# OledAdapter.net
KiCad netlist of a schematic drawn in EAGLE
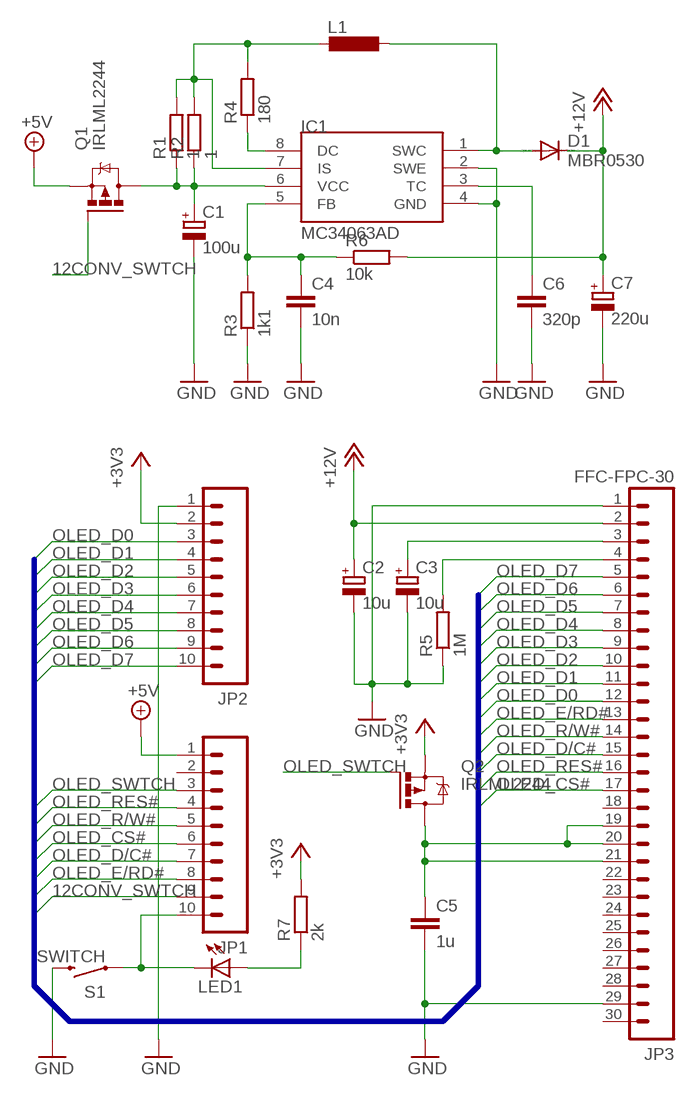
[diagram p0: schematic, sheet 1]

(export (version "E")
  (design (tool "Eeschema 10.0.6"))
  (components
    (comp (ref "C1")
      (value "100u")
      (footprint "eagle-import:UD-6,3X7,7_NICHICON")
      (libsource (lib "eagle-import") (part "CPOL-EUUD-6,3X7,7"))
    )
    (comp (ref "C2")
      (value "10u")
      (footprint "eagle-import:UD-4X5,8_NICHICON")
      (libsource (lib "eagle-import") (part "CPOL-EUUD-4X5,8"))
    )
    (comp (ref "C3")
      (value "10u")
      (footprint "eagle-import:UD-4X5,8_NICHICON")
      (libsource (lib "eagle-import") (part "CPOL-EUUD-4X5,8"))
    )
    (comp (ref "C4")
      (value "10n")
      (footprint "eagle-import:C0805")
      (libsource (lib "eagle-import") (part "C-EUC0805"))
    )
    (comp (ref "C5")
      (value "1u")
      (footprint "eagle-import:C1206")
      (libsource (lib "eagle-import") (part "C-EUC1206"))
    )
    (comp (ref "C6")
      (value "320p")
      (footprint "eagle-import:C0805")
      (libsource (lib "eagle-import") (part "C-EUC0805"))
    )
    (comp (ref "C7")
      (value "220u")
      (footprint "eagle-import:UD-6,3X7,7_NICHICON")
      (libsource (lib "eagle-import") (part "CPOL-EUUD-6,3X7,7"))
    )
    (comp (ref "D1")
      (value "MBR0530")
      (footprint "eagle-import:SOD123")
      (libsource (lib "eagle-import") (part "MBR0520LT"))
    )
    (comp (ref "IC1")
      (value "MC34063AD")
      (footprint "eagle-import:SOIC8")
      (libsource (lib "eagle-import") (part "MC34063AD"))
    )
    (comp (ref "JP1")
      (value "M10SILK_FEMALE_PTH")
      (footprint "eagle-import:1X10")
      (libsource (lib "eagle-import") (part "M10SILK_FEMALE_PTH"))
    )
    (comp (ref "JP2")
      (value "M10SILK_FEMALE_PTH")
      (footprint "eagle-import:1X10")
      (libsource (lib "eagle-import") (part "M10SILK_FEMALE_PTH"))
    )
    (comp (ref "JP3")
      (value "FFC-FPC-30")
      (footprint "eagle-import:FFC-FPC-30V")
      (libsource (lib "eagle-import") (part "FFC-FPC-30"))
    )
    (comp (ref "L1")
      (value "L-EUL8530M")
      (footprint "eagle-import:L8530M")
      (libsource (lib "eagle-import") (part "L-EUL8530M"))
    )
    (comp (ref "LED1")
      (value "LEDSML1206")
      (footprint "eagle-import:SML1206")
      (libsource (lib "eagle-import") (part "LEDSML1206"))
    )
    (comp (ref "Q1")
      (value "IRLML2244")
      (footprint "eagle-import:MICRO3")
      (libsource (lib "eagle-import") (part "IRLML5203"))
    )
    (comp (ref "Q2")
      (value "IRLML2244")
      (footprint "eagle-import:MICRO3")
      (libsource (lib "eagle-import") (part "IRLML5203"))
    )
    (comp (ref "R1")
      (value "1")
      (footprint "eagle-import:R0805")
      (libsource (lib "eagle-import") (part "R-EU_R0805"))
    )
    (comp (ref "R2")
      (value "1")
      (footprint "eagle-import:R0805")
      (libsource (lib "eagle-import") (part "R-EU_R0805"))
    )
    (comp (ref "R3")
      (value "1k1")
      (footprint "eagle-import:R0805")
      (libsource (lib "eagle-import") (part "R-EU_R0805"))
    )
    (comp (ref "R4")
      (value "180")
      (footprint "eagle-import:R0805")
      (libsource (lib "eagle-import") (part "R-EU_R0805"))
    )
    (comp (ref "R5")
      (value "1M")
      (footprint "eagle-import:M1206")
      (libsource (lib "eagle-import") (part "R-EU_M1206"))
    )
    (comp (ref "R6")
      (value "10k")
      (footprint "eagle-import:R0805")
      (libsource (lib "eagle-import") (part "R-EU_R0805"))
    )
    (comp (ref "R7")
      (value "2k")
      (footprint "eagle-import:R0805")
      (libsource (lib "eagle-import") (part "R-EU_R0805"))
    )
    (comp (ref "S1")
      (value "SWITCH")
      (footprint "eagle-import:TACTILE-SWITCH-1101NE")
      (libsource (lib "eagle-import") (part "SWITCH-MOMENTARY-2SMD-1101NE"))
    )
  )
  (nets
    (net (code "1") (name "+3V3") (class "Default")
      (node (ref "JP2") (pin "2") (pinfunction "2_2") (pintype "passive"))
      (node (ref "Q2") (pin "2") (pinfunction "S_2") (pintype "passive"))
      (node (ref "R7") (pin "2") (pinfunction "2_2") (pintype "passive"))
    )
    (net (code "2") (name "+5V") (class "Default")
      (node (ref "JP1") (pin "1") (pinfunction "1_1") (pintype "passive"))
      (node (ref "Q1") (pin "2") (pinfunction "S_2") (pintype "passive"))
    )
    (net (code "3") (name "+12V") (class "Default")
      (node (ref "C2") (pin "+") (pinfunction "+_+") (pintype "passive"))
      (node (ref "C7") (pin "+") (pinfunction "+_+") (pintype "passive"))
      (node (ref "D1") (pin "C") (pinfunction "C_C") (pintype "passive"))
      (node (ref "JP3") (pin "2") (pinfunction "2_2") (pintype "passive"))
      (node (ref "R6") (pin "2") (pinfunction "2_2") (pintype "passive"))
    )
    (net (code "4") (name "/12CONV_SWTCH") (class "Default")
      (node (ref "JP1") (pin "9") (pinfunction "9_9") (pintype "passive"))
      (node (ref "Q1") (pin "1") (pinfunction "G_1") (pintype "passive"))
    )
    (net (code "5") (name "/OLED_CS#") (class "Default")
      (node (ref "JP1") (pin "6") (pinfunction "6_6") (pintype "passive"))
      (node (ref "JP3") (pin "17") (pinfunction "17_17") (pintype "passive"))
    )
    (net (code "6") (name "/OLED_D0") (class "Default")
      (node (ref "JP2") (pin "3") (pinfunction "3_3") (pintype "passive"))
      (node (ref "JP3") (pin "12") (pinfunction "12_12") (pintype "passive"))
    )
    (net (code "7") (name "/OLED_D1") (class "Default")
      (node (ref "JP2") (pin "4") (pinfunction "4_4") (pintype "passive"))
      (node (ref "JP3") (pin "11") (pinfunction "11_11") (pintype "passive"))
    )
    (net (code "8") (name "/OLED_D2") (class "Default")
      (node (ref "JP2") (pin "5") (pinfunction "5_5") (pintype "passive"))
      (node (ref "JP3") (pin "10") (pinfunction "10_10") (pintype "passive"))
    )
    (net (code "9") (name "/OLED_D3") (class "Default")
      (node (ref "JP2") (pin "6") (pinfunction "6_6") (pintype "passive"))
      (node (ref "JP3") (pin "9") (pinfunction "9_9") (pintype "passive"))
    )
    (net (code "10") (name "/OLED_D4") (class "Default")
      (node (ref "JP2") (pin "7") (pinfunction "7_7") (pintype "passive"))
      (node (ref "JP3") (pin "8") (pinfunction "8_8") (pintype "passive"))
    )
    (net (code "11") (name "/OLED_D5") (class "Default")
      (node (ref "JP2") (pin "8") (pinfunction "8_8") (pintype "passive"))
      (node (ref "JP3") (pin "7") (pinfunction "7_7") (pintype "passive"))
    )
    (net (code "12") (name "/OLED_D6") (class "Default")
      (node (ref "JP2") (pin "9") (pinfunction "9_9") (pintype "passive"))
      (node (ref "JP3") (pin "6") (pinfunction "6_6") (pintype "passive"))
    )
    (net (code "13") (name "/OLED_D7") (class "Default")
      (node (ref "JP2") (pin "10") (pinfunction "10_10") (pintype "passive"))
      (node (ref "JP3") (pin "5") (pinfunction "5_5") (pintype "passive"))
    )
    (net (code "14") (name "/OLED_D{slash}C#") (class "Default")
      (node (ref "JP1") (pin "7") (pinfunction "7_7") (pintype "passive"))
      (node (ref "JP3") (pin "15") (pinfunction "15_15") (pintype "passive"))
    )
    (net (code "15") (name "/OLED_E{slash}RD#") (class "Default")
      (node (ref "JP1") (pin "8") (pinfunction "8_8") (pintype "passive"))
      (node (ref "JP3") (pin "13") (pinfunction "13_13") (pintype "passive"))
    )
    (net (code "16") (name "/OLED_RES#") (class "Default")
      (node (ref "JP1") (pin "4") (pinfunction "4_4") (pintype "passive"))
      (node (ref "JP3") (pin "16") (pinfunction "16_16") (pintype "passive"))
    )
    (net (code "17") (name "/OLED_R{slash}W#") (class "Default")
      (node (ref "JP1") (pin "5") (pinfunction "5_5") (pintype "passive"))
      (node (ref "JP3") (pin "14") (pinfunction "14_14") (pintype "passive"))
    )
    (net (code "18") (name "/OLED_SWTCH") (class "Default")
      (node (ref "JP1") (pin "3") (pinfunction "3_3") (pintype "passive"))
      (node (ref "Q2") (pin "1") (pinfunction "G_1") (pintype "passive"))
    )
    (net (code "19") (name "GND") (class "Default")
      (node (ref "C1") (pin "-") (pinfunction "-_-") (pintype "passive"))
      (node (ref "C2") (pin "-") (pinfunction "-_-") (pintype "passive"))
      (node (ref "C3") (pin "-") (pinfunction "-_-") (pintype "passive"))
      (node (ref "C4") (pin "2") (pinfunction "2_2") (pintype "passive"))
      (node (ref "C5") (pin "2") (pinfunction "2_2") (pintype "passive"))
      (node (ref "C6") (pin "2") (pinfunction "2_2") (pintype "passive"))
      (node (ref "C7") (pin "-") (pinfunction "-_-") (pintype "passive"))
      (node (ref "IC1") (pin "2") (pinfunction "SWE_2") (pintype "passive"))
      (node (ref "IC1") (pin "4") (pinfunction "GND_4") (pintype "passive"))
      (node (ref "JP2") (pin "1") (pinfunction "1_1") (pintype "passive"))
      (node (ref "JP3") (pin "1") (pinfunction "1_1") (pintype "passive"))
      (node (ref "JP3") (pin "29") (pinfunction "29_29") (pintype "passive"))
      (node (ref "R3") (pin "1") (pinfunction "1_1") (pintype "passive"))
      (node (ref "R5") (pin "1") (pinfunction "1_1") (pintype "passive"))
      (node (ref "S1") (pin "2") (pinfunction "2_2") (pintype "passive"))
    )
    (net (code "20") (name "Net-(C3-Pad+)") (class "Default")
      (node (ref "C3") (pin "+") (pinfunction "+_+") (pintype "passive"))
      (node (ref "JP3") (pin "3") (pinfunction "3_3") (pintype "passive"))
    )
    (net (code "21") (name "Net-(IC1-DC)") (class "Default")
      (node (ref "IC1") (pin "8") (pinfunction "DC_8") (pintype "passive"))
      (node (ref "R4") (pin "1") (pinfunction "1_1") (pintype "passive"))
    )
    (net (code "22") (name "Net-(IC1-FB)") (class "Default")
      (node (ref "C4") (pin "1") (pinfunction "1_1") (pintype "passive"))
      (node (ref "IC1") (pin "5") (pinfunction "FB_5") (pintype "passive"))
      (node (ref "R3") (pin "2") (pinfunction "2_2") (pintype "passive"))
      (node (ref "R6") (pin "1") (pinfunction "1_1") (pintype "passive"))
    )
    (net (code "23") (name "Net-(IC1-IS)") (class "Default")
      (node (ref "IC1") (pin "7") (pinfunction "IS_7") (pintype "passive"))
      (node (ref "L1") (pin "2") (pinfunction "2_2") (pintype "passive"))
      (node (ref "R1") (pin "2") (pinfunction "2_2") (pintype "passive"))
      (node (ref "R2") (pin "2") (pinfunction "2_2") (pintype "passive"))
      (node (ref "R4") (pin "2") (pinfunction "2_2") (pintype "passive"))
    )
    (net (code "24") (name "Net-(IC1-SWC)") (class "Default")
      (node (ref "D1") (pin "A") (pinfunction "A_A") (pintype "passive"))
      (node (ref "IC1") (pin "1") (pinfunction "SWC_1") (pintype "passive"))
      (node (ref "L1") (pin "1") (pinfunction "1_1") (pintype "passive"))
    )
    (net (code "25") (name "Net-(IC1-TC)") (class "Default")
      (node (ref "C6") (pin "1") (pinfunction "1_1") (pintype "passive"))
      (node (ref "IC1") (pin "3") (pinfunction "TC_3") (pintype "passive"))
    )
    (net (code "26") (name "Net-(IC1-VCC)") (class "Default")
      (node (ref "C1") (pin "+") (pinfunction "+_+") (pintype "passive"))
      (node (ref "IC1") (pin "6") (pinfunction "VCC_6") (pintype "passive"))
      (node (ref "Q1") (pin "3") (pinfunction "D_3") (pintype "passive"))
      (node (ref "R1") (pin "1") (pinfunction "1_1") (pintype "passive"))
      (node (ref "R2") (pin "1") (pinfunction "1_1") (pintype "passive"))
    )
    (net (code "27") (name "Net-(JP1-Pad10)") (class "Default")
      (node (ref "JP1") (pin "10") (pinfunction "10_10") (pintype "passive"))
      (node (ref "LED1") (pin "C") (pinfunction "C_C") (pintype "passive"))
      (node (ref "S1") (pin "1") (pinfunction "1_1") (pintype "passive"))
    )
    (net (code "28") (name "Net-(JP3-Pad4)") (class "Default")
      (node (ref "JP3") (pin "4") (pinfunction "4_4") (pintype "passive"))
      (node (ref "R5") (pin "2") (pinfunction "2_2") (pintype "passive"))
    )
    (net (code "29") (name "Net-(LED1-PadA)") (class "Default")
      (node (ref "LED1") (pin "A") (pinfunction "A_A") (pintype "passive"))
      (node (ref "R7") (pin "1") (pinfunction "1_1") (pintype "passive"))
    )
    (net (code "30") (name "Net-(Q2-D)") (class "Default")
      (node (ref "C5") (pin "1") (pinfunction "1_1") (pintype "passive"))
      (node (ref "JP3") (pin "19") (pinfunction "19_19") (pintype "passive"))
      (node (ref "JP3") (pin "20") (pinfunction "20_20") (pintype "passive"))
      (node (ref "JP3") (pin "21") (pinfunction "21_21") (pintype "passive"))
      (node (ref "Q2") (pin "3") (pinfunction "D_3") (pintype "passive"))
    )
    (net (code "31") (name "unconnected-(JP1-Pad2)") (class "Default")
      (node (ref "JP1") (pin "2") (pinfunction "2_2") (pintype "passive"))
    )
    (net (code "32") (name "unconnected-(JP3-Pad18)") (class "Default")
      (node (ref "JP3") (pin "18") (pinfunction "18_18") (pintype "passive"))
    )
    (net (code "33") (name "unconnected-(JP3-Pad22)") (class "Default")
      (node (ref "JP3") (pin "22") (pinfunction "22_22") (pintype "passive"))
    )
    (net (code "34") (name "unconnected-(JP3-Pad23)") (class "Default")
      (node (ref "JP3") (pin "23") (pinfunction "23_23") (pintype "passive"))
    )
    (net (code "35") (name "unconnected-(JP3-Pad24)") (class "Default")
      (node (ref "JP3") (pin "24") (pinfunction "24_24") (pintype "passive"))
    )
    (net (code "36") (name "unconnected-(JP3-Pad25)") (class "Default")
      (node (ref "JP3") (pin "25") (pinfunction "25_25") (pintype "passive"))
    )
    (net (code "37") (name "unconnected-(JP3-Pad26)") (class "Default")
      (node (ref "JP3") (pin "26") (pinfunction "26_26") (pintype "passive"))
    )
    (net (code "38") (name "unconnected-(JP3-Pad27)") (class "Default")
      (node (ref "JP3") (pin "27") (pinfunction "27_27") (pintype "passive"))
    )
    (net (code "39") (name "unconnected-(JP3-Pad28)") (class "Default")
      (node (ref "JP3") (pin "28") (pinfunction "28_28") (pintype "passive"))
    )
    (net (code "40") (name "unconnected-(JP3-Pad30)") (class "Default")
      (node (ref "JP3") (pin "30") (pinfunction "30_30") (pintype "passive"))
    )
  )
)
